# CMSIS-DAP_JX_copy.net
KiCad netlist of a schematic drawn in Altium Designer
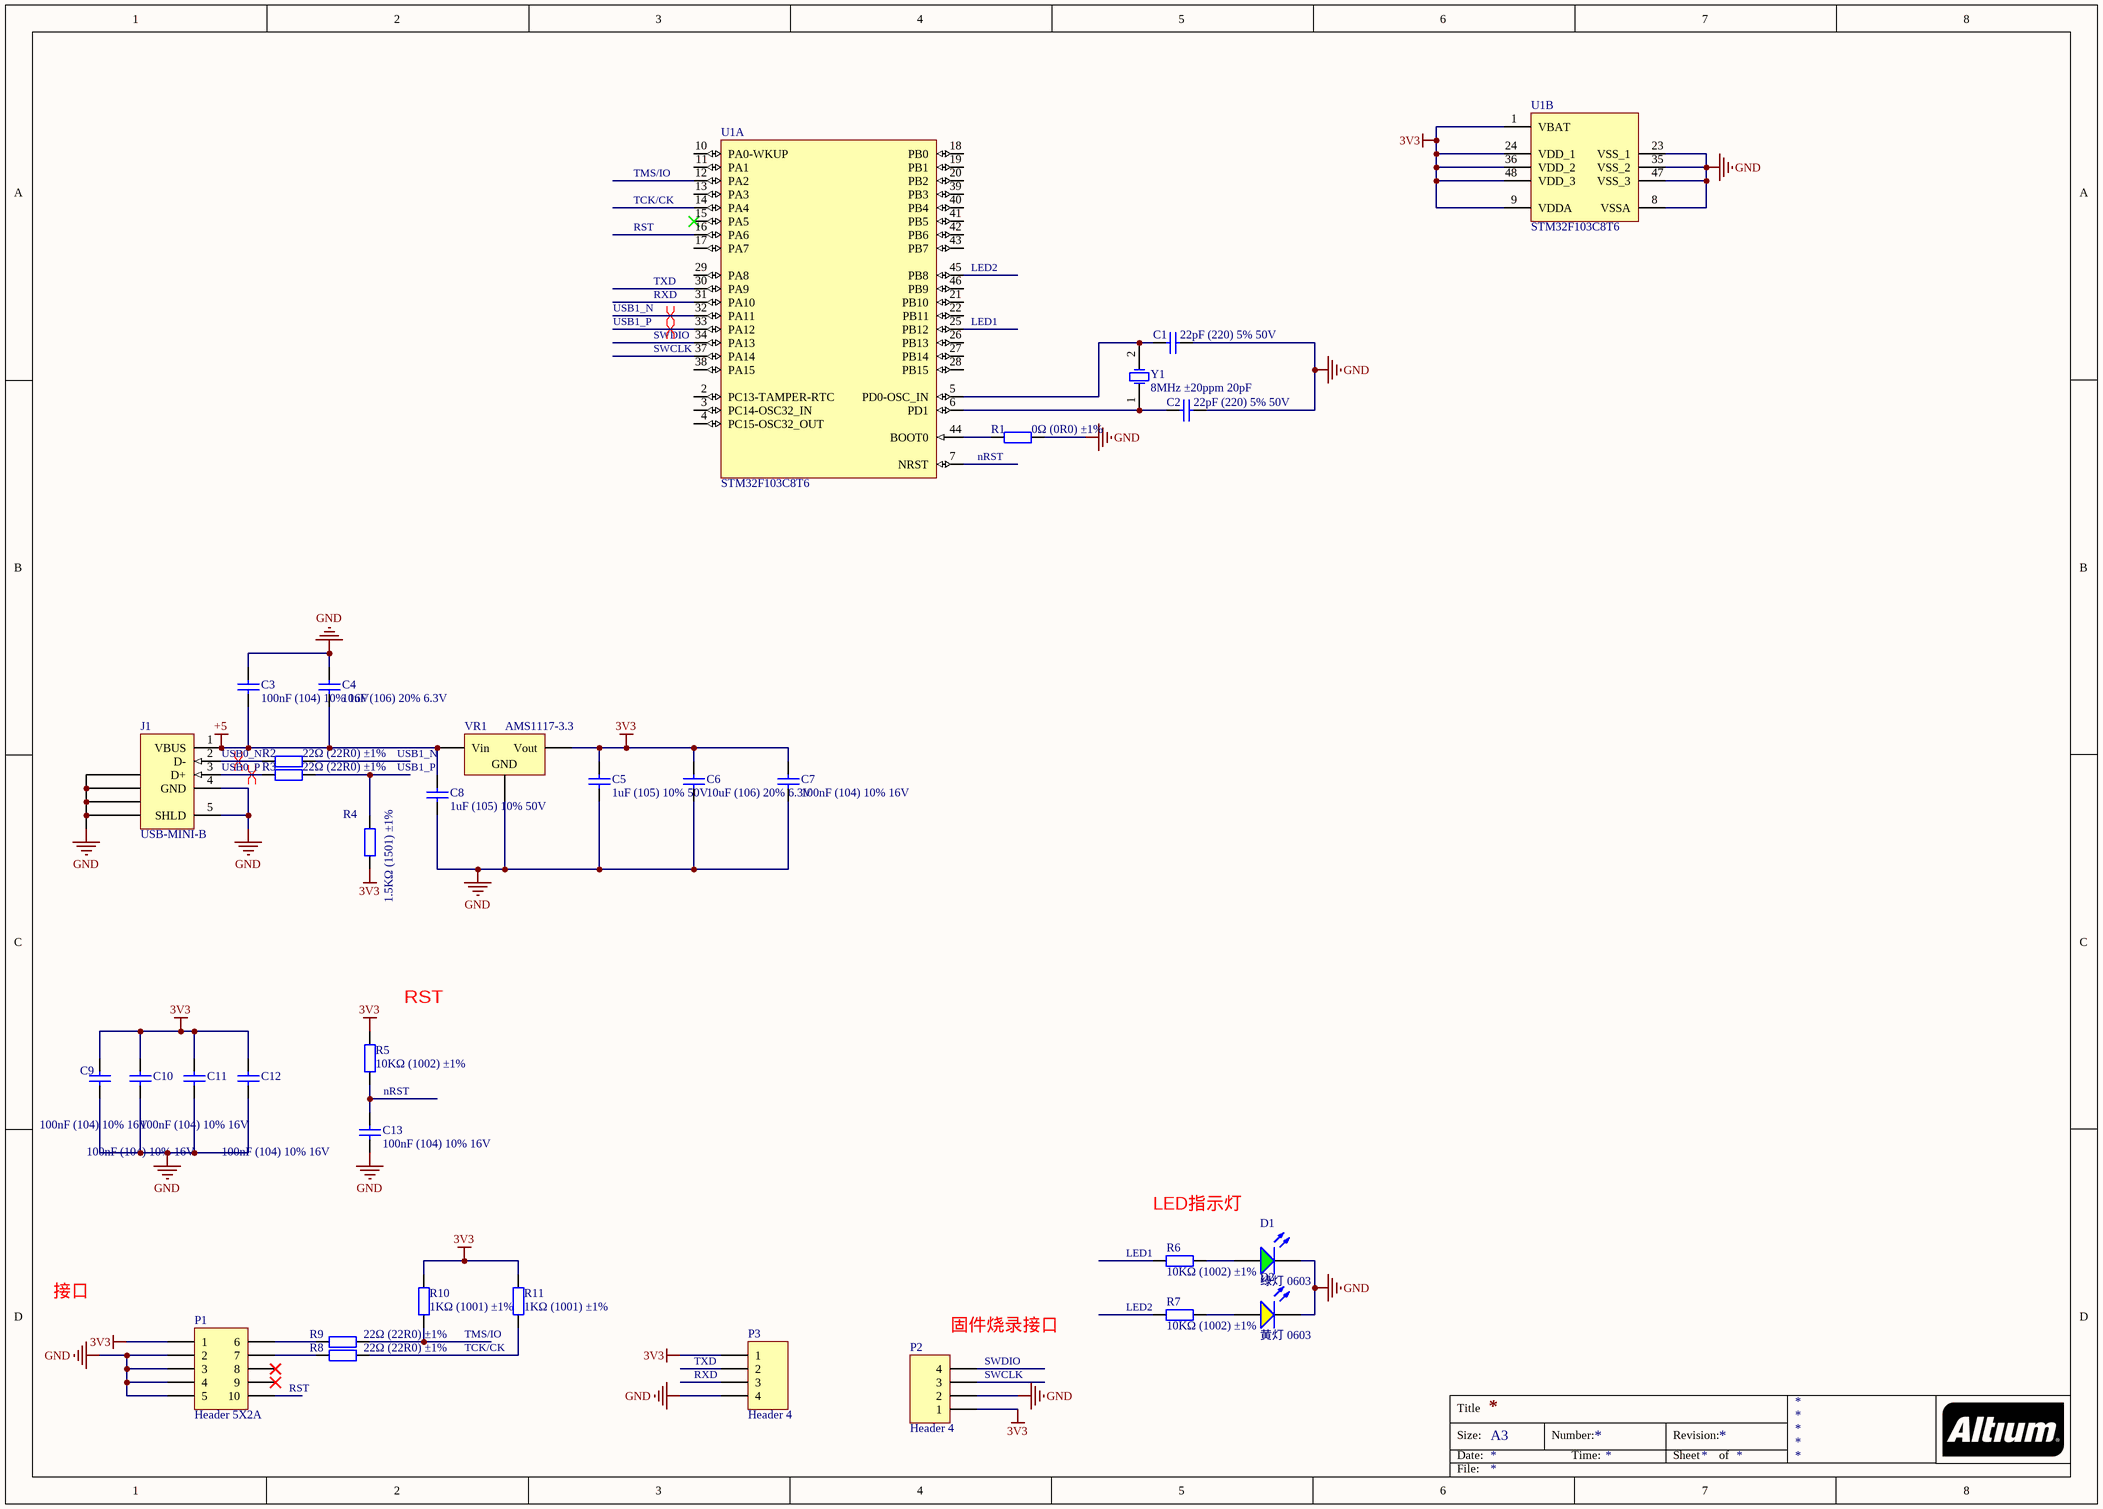
[diagram p0: CMSIS-DAP_JX+copy.schdoc]

(export (version "E")
  (design (tool "Eeschema 10.0.6"))
  (components
    (comp (ref "C1")
      (value "22pF (220) 5% 50V")
      (footprint "0402_C")
      (description "贴片电容")
      (libsource (lib "Miscellaneous Devices LC") (part "0402 22pF (220) 5% 50V"))
    )
    (comp (ref "C2")
      (value "22pF (220) 5% 50V")
      (footprint "0402_C")
      (description "贴片电容")
      (libsource (lib "Miscellaneous Devices LC") (part "0402 22pF (220) 5% 50V"))
    )
    (comp (ref "C3")
      (value "100nF (104) 10% 16V")
      (footprint "0402_C")
      (description "贴片电容")
      (libsource (lib "Miscellaneous Devices LC") (part "0402 100nF (104) 10% 16V"))
    )
    (comp (ref "C4")
      (value "10uF (106) 20% 6.3V")
      (footprint "0402_C")
      (description "贴片电容")
      (libsource (lib "Miscellaneous Devices LC") (part "0402 10uF (106) 20% 6.3V"))
    )
    (comp (ref "C5")
      (value "1uF (105) 10% 50V")
      (footprint "0603_C")
      (description "贴片电容")
      (libsource (lib "Miscellaneous Devices LC") (part "0603 1uF (105) 10% 50V"))
    )
    (comp (ref "C6")
      (value "10uF (106) 20% 6.3V")
      (footprint "0402_C")
      (description "贴片电容")
      (libsource (lib "Miscellaneous Devices LC") (part "0402 10uF (106) 20% 6.3V"))
    )
    (comp (ref "C7")
      (value "100nF (104) 10% 16V")
      (footprint "0402_C")
      (description "贴片电容")
      (libsource (lib "Miscellaneous Devices LC") (part "0402 100nF (104) 10% 16V"))
    )
    (comp (ref "C8")
      (value "1uF (105) 10% 50V")
      (footprint "0603_C")
      (description "贴片电容")
      (libsource (lib "Miscellaneous Devices LC") (part "0603 1uF (105) 10% 50V"))
    )
    (comp (ref "C9")
      (value "100nF (104) 10% 16V")
      (footprint "0402_C")
      (description "贴片电容")
      (libsource (lib "Miscellaneous Devices LC") (part "0402 100nF (104) 10% 16V"))
    )
    (comp (ref "C10")
      (value "100nF (104) 10% 16V")
      (footprint "0402_C")
      (description "贴片电容")
      (libsource (lib "Miscellaneous Devices LC") (part "0402 100nF (104) 10% 16V"))
    )
    (comp (ref "C11")
      (value "100nF (104) 10% 16V")
      (footprint "0402_C")
      (description "贴片电容")
      (libsource (lib "Miscellaneous Devices LC") (part "0402 100nF (104) 10% 16V"))
    )
    (comp (ref "C12")
      (value "100nF (104) 10% 16V")
      (footprint "0402_C")
      (description "贴片电容")
      (libsource (lib "Miscellaneous Devices LC") (part "0402 100nF (104) 10% 16V"))
    )
    (comp (ref "C13")
      (value "100nF (104) 10% 16V")
      (footprint "0402_C")
      (description "贴片电容")
      (libsource (lib "Miscellaneous Devices LC") (part "0402 100nF (104) 10% 16V"))
    )
    (comp (ref "D1")
      (value "绿灯 0603")
      (footprint "0603_LED_S1")
      (description "发光二极管")
      (libsource (lib "Miscellaneous Devices LC") (part "0603 绿灯"))
    )
    (comp (ref "D2")
      (value "黄灯 0603")
      (footprint "0603_LED_S1")
      (description "发光二极管")
      (libsource (lib "Miscellaneous Devices LC") (part "0603 黄灯"))
    )
    (comp (ref "J1")
      (value "USB-MINI-B")
      (footprint "U-G-04WD-W-01 公头")
      (description "USB 2.0, Right Angle, SMT, A Type, Receptacle, 5 Position, Black")
      (fields (field (name "PUBLISHER") "Altium Limited"))
      (libsource (lib "Sparks") (part "USB-MINI-B"))
    )
    (comp (ref "P1")
      (value "Header 5X2A")
      (footprint "SMT HEADER 5*2")
      (description "Header, 5-Pin, Dual row")
      (fields (field (name "PUBLISHER") "Altium Limited"))
      (libsource (lib "Miscellaneous Connectors") (part "Header 5X2A"))
    )
    (comp (ref "P2")
      (value "Header 4")
      (footprint "HDR1X4")
      (description "Header, 4-Pin")
      (fields (field (name "PUBLISHER") "Altium Limited"))
      (libsource (lib "") (part "Header 4_1"))
    )
    (comp (ref "P3")
      (value "Header 4")
      (footprint "HDR1X4")
      (description "Header, 4-Pin")
      (fields (field (name "PUBLISHER") "Altium Limited"))
      (libsource (lib "Sparks") (part "Header 4"))
    )
    (comp (ref "R1")
      (value "0Ω (0R0) ±1%")
      (footprint "0402_R")
      (description "贴片电阻")
      (libsource (lib "Miscellaneous Devices LC") (part "0402 0Ω (0R0) 1%"))
    )
    (comp (ref "R2")
      (value "22Ω (22R0) ±1%")
      (footprint "0402_R")
      (description "贴片电阻")
      (libsource (lib "Miscellaneous Devices LC") (part "0402 22Ω (22R0) 1%"))
    )
    (comp (ref "R3")
      (value "22Ω (22R0) ±1%")
      (footprint "0402_R")
      (description "贴片电阻")
      (libsource (lib "Miscellaneous Devices LC") (part "0402 22Ω (22R0) 1%"))
    )
    (comp (ref "R4")
      (value "1.5KΩ (1501) ±1%")
      (footprint "0402_R")
      (description "贴片电阻")
      (libsource (lib "Miscellaneous Devices LC") (part "0402 1.5KΩ (1501) 1%"))
    )
    (comp (ref "R5")
      (value "10KΩ (1002) ±1%")
      (footprint "0402_R")
      (description "贴片电阻")
      (libsource (lib "Miscellaneous Devices LC") (part "0402 10KΩ (1002) 1%"))
    )
    (comp (ref "R6")
      (value "10KΩ (1002) ±1%")
      (footprint "0402_R")
      (description "贴片电阻")
      (libsource (lib "") (part "0402 10KΩ (1002) 1%_1"))
    )
    (comp (ref "R7")
      (value "10KΩ (1002) ±1%")
      (footprint "0402_R")
      (description "贴片电阻")
      (libsource (lib "") (part "0402 10KΩ (1002) 1%_1"))
    )
    (comp (ref "R8")
      (value "22Ω (22R0) ±1%")
      (footprint "0402_R")
      (description "贴片电阻")
      (libsource (lib "Miscellaneous Devices LC") (part "0402 22Ω (22R0) 1%"))
    )
    (comp (ref "R9")
      (value "22Ω (22R0) ±1%")
      (footprint "0402_R")
      (description "贴片电阻")
      (libsource (lib "Miscellaneous Devices LC") (part "0402 22Ω (22R0) 1%"))
    )
    (comp (ref "R10")
      (value "1KΩ (1001) ±1%")
      (footprint "0402_R")
      (description "贴片电阻")
      (libsource (lib "Miscellaneous Devices LC") (part "0402 1KΩ (1001) 1%"))
    )
    (comp (ref "R11")
      (value "1KΩ (1001) ±1%")
      (footprint "0402_R")
      (description "贴片电阻")
      (libsource (lib "Miscellaneous Devices LC") (part "0402 1KΩ (1001) 1%"))
    )
    (comp (ref "U1")
      (value "STM32F103C8T6")
      (footprint "LQFP-48_7x7x05P")
      (description "ARM")
      (libsource (lib "Miscellaneous Devices LC") (part "STM32F103C8T6"))
    )
    (comp (ref "VR1")
      (value "AMS1117-3.3")
      (footprint "SOT-223")
      (description "低压差线性稳压(LDO)")
      (libsource (lib "Miscellaneous Devices LC") (part "SOT-223 AMS1117-3.3"))
    )
    (comp (ref "Y1")
      (value "8MHz ±20ppm 20pF")
      (footprint "SMD-5032_2P")
      (description "贴片晶振")
      (libsource (lib "Miscellaneous Devices LC") (part "SMD-5032_2P 8MHz 20ppm 20pF"))
    )
  )
  (nets
    (net (code "1") (name "+5") (class "Default")
      (node (ref "C3") (pin "1") (pinfunction "1_1") (pintype "passive"))
      (node (ref "C4") (pin "1") (pinfunction "1_1") (pintype "passive"))
      (node (ref "C8") (pin "2") (pinfunction "2_2") (pintype "passive"))
      (node (ref "J1") (pin "1") (pinfunction "VBUS_1") (pintype "power_in"))
      (node (ref "VR1") (pin "3") (pinfunction "Vin_3") (pintype "passive"))
    )
    (net (code "2") (name "/LED1") (class "Default")
      (node (ref "R6") (pin "1") (pinfunction "1_1") (pintype "passive"))
      (node (ref "U1") (pin "25") (pinfunction "PB12_25") (pintype "bidirectional"))
    )
    (net (code "3") (name "/LED2") (class "Default")
      (node (ref "R7") (pin "1") (pinfunction "1_1") (pintype "passive"))
      (node (ref "U1") (pin "45") (pinfunction "PB8_45") (pintype "bidirectional"))
    )
    (net (code "4") (name "/RST") (class "Default")
      (node (ref "P1") (pin "10") (pinfunction "10_10") (pintype "passive"))
      (node (ref "U1") (pin "16") (pinfunction "PA6_16") (pintype "bidirectional"))
    )
    (net (code "5") (name "/RXD") (class "Default")
      (node (ref "P3") (pin "3") (pinfunction "3_3") (pintype "passive"))
      (node (ref "U1") (pin "31") (pinfunction "PA10_31") (pintype "bidirectional"))
    )
    (net (code "6") (name "/SWCLK") (class "Default")
      (node (ref "P2") (pin "3") (pinfunction "3_3") (pintype "passive"))
      (node (ref "U1") (pin "37") (pinfunction "PA14_37") (pintype "bidirectional"))
    )
    (net (code "7") (name "/SWDIO") (class "Default")
      (node (ref "P2") (pin "4") (pinfunction "4_4") (pintype "passive"))
      (node (ref "U1") (pin "34") (pinfunction "PA13_34") (pintype "bidirectional"))
    )
    (net (code "8") (name "/TCK{slash}CK") (class "Default")
      (node (ref "R11") (pin "1") (pinfunction "1_1") (pintype "passive"))
      (node (ref "R8") (pin "2") (pinfunction "2_2") (pintype "passive"))
      (node (ref "U1") (pin "14") (pinfunction "PA4_14") (pintype "bidirectional"))
    )
    (net (code "9") (name "/TMS{slash}IO") (class "Default")
      (node (ref "R10") (pin "1") (pinfunction "1_1") (pintype "passive"))
      (node (ref "R9") (pin "2") (pinfunction "2_2") (pintype "passive"))
      (node (ref "U1") (pin "12") (pinfunction "PA2_12") (pintype "bidirectional"))
    )
    (net (code "10") (name "/TXD") (class "Default")
      (node (ref "P3") (pin "2") (pinfunction "2_2") (pintype "passive"))
      (node (ref "U1") (pin "30") (pinfunction "PA9_30") (pintype "bidirectional"))
    )
    (net (code "11") (name "/USB0_N") (class "Default")
      (node (ref "J1") (pin "2") (pinfunction "D-_2") (pintype "input"))
      (node (ref "R2") (pin "1") (pinfunction "1_1") (pintype "passive"))
    )
    (net (code "12") (name "/USB0_P") (class "Default")
      (node (ref "J1") (pin "3") (pinfunction "D+_3") (pintype "input"))
      (node (ref "R3") (pin "1") (pinfunction "1_1") (pintype "passive"))
    )
    (net (code "13") (name "/USB1_N") (class "Default")
      (node (ref "R2") (pin "2") (pinfunction "2_2") (pintype "passive"))
      (node (ref "U1") (pin "32") (pinfunction "PA11_32") (pintype "bidirectional"))
    )
    (net (code "14") (name "/USB1_P") (class "Default")
      (node (ref "R3") (pin "2") (pinfunction "2_2") (pintype "passive"))
      (node (ref "R4") (pin "2") (pinfunction "2_2") (pintype "passive"))
      (node (ref "U1") (pin "33") (pinfunction "PA12_33") (pintype "bidirectional"))
    )
    (net (code "15") (name "/nRST") (class "Default")
      (node (ref "C13") (pin "2") (pinfunction "2_2") (pintype "passive"))
      (node (ref "R5") (pin "1") (pinfunction "1_1") (pintype "passive"))
      (node (ref "U1") (pin "7") (pinfunction "NRST_7") (pintype "bidirectional"))
    )
    (net (code "16") (name "3V3") (class "Default")
      (node (ref "C10") (pin "2") (pinfunction "2_2") (pintype "passive"))
      (node (ref "C11") (pin "2") (pinfunction "2_2") (pintype "passive"))
      (node (ref "C12") (pin "2") (pinfunction "2_2") (pintype "passive"))
      (node (ref "C5") (pin "2") (pinfunction "2_2") (pintype "passive"))
      (node (ref "C6") (pin "2") (pinfunction "2_2") (pintype "passive"))
      (node (ref "C7") (pin "2") (pinfunction "2_2") (pintype "passive"))
      (node (ref "C9") (pin "2") (pinfunction "2_2") (pintype "passive"))
      (node (ref "P1") (pin "1") (pinfunction "1_1") (pintype "passive"))
      (node (ref "P2") (pin "1") (pinfunction "1_1") (pintype "passive"))
      (node (ref "P3") (pin "1") (pinfunction "1_1") (pintype "passive"))
      (node (ref "R10") (pin "2") (pinfunction "2_2") (pintype "passive"))
      (node (ref "R11") (pin "2") (pinfunction "2_2") (pintype "passive"))
      (node (ref "R4") (pin "1") (pinfunction "1_1") (pintype "passive"))
      (node (ref "R5") (pin "2") (pinfunction "2_2") (pintype "passive"))
      (node (ref "U1") (pin "1") (pinfunction "VBAT_1") (pintype "power_in"))
      (node (ref "U1") (pin "24") (pinfunction "VDD_1_24") (pintype "power_in"))
      (node (ref "U1") (pin "36") (pinfunction "VDD_2_36") (pintype "power_in"))
      (node (ref "U1") (pin "48") (pinfunction "VDD_3_48") (pintype "power_in"))
      (node (ref "U1") (pin "9") (pinfunction "VDDA_9") (pintype "power_in"))
      (node (ref "VR1") (pin "2") (pinfunction "Vout_2") (pintype "passive"))
    )
    (net (code "17") (name "GND") (class "Default")
      (node (ref "C1") (pin "2") (pinfunction "2_2") (pintype "passive"))
      (node (ref "C10") (pin "1") (pinfunction "1_1") (pintype "passive"))
      (node (ref "C11") (pin "1") (pinfunction "1_1") (pintype "passive"))
      (node (ref "C12") (pin "1") (pinfunction "1_1") (pintype "passive"))
      (node (ref "C13") (pin "1") (pinfunction "1_1") (pintype "passive"))
      (node (ref "C2") (pin "2") (pinfunction "2_2") (pintype "passive"))
      (node (ref "C3") (pin "2") (pinfunction "2_2") (pintype "passive"))
      (node (ref "C4") (pin "2") (pinfunction "2_2") (pintype "passive"))
      (node (ref "C5") (pin "1") (pinfunction "1_1") (pintype "passive"))
      (node (ref "C6") (pin "1") (pinfunction "1_1") (pintype "passive"))
      (node (ref "C7") (pin "1") (pinfunction "1_1") (pintype "passive"))
      (node (ref "C8") (pin "1") (pinfunction "1_1") (pintype "passive"))
      (node (ref "C9") (pin "1") (pinfunction "1_1") (pintype "passive"))
      (node (ref "D1") (pin "K") (pinfunction "K_K") (pintype "passive"))
      (node (ref "D2") (pin "K") (pinfunction "K_K") (pintype "passive"))
      (node (ref "J1") (pin "4") (pinfunction "GND_4") (pintype "power_in"))
      (node (ref "J1") (pin "5") (pinfunction "SHLD_5") (pintype "passive"))
      (node (ref "J1") (pin "6") (pinfunction "SHLD_6") (pintype "passive"))
      (node (ref "J1") (pin "7") (pinfunction "SHLD_7") (pintype "passive"))
      (node (ref "J1") (pin "8") (pinfunction "SHLD_8") (pintype "passive"))
      (node (ref "J1") (pin "9") (pinfunction "SHLD_9") (pintype "passive"))
      (node (ref "P1") (pin "2") (pinfunction "2_2") (pintype "passive"))
      (node (ref "P1") (pin "3") (pinfunction "3_3") (pintype "passive"))
      (node (ref "P1") (pin "4") (pinfunction "4_4") (pintype "passive"))
      (node (ref "P1") (pin "5") (pinfunction "5_5") (pintype "passive"))
      (node (ref "P2") (pin "2") (pinfunction "2_2") (pintype "passive"))
      (node (ref "P3") (pin "4") (pinfunction "4_4") (pintype "passive"))
      (node (ref "R1") (pin "2") (pinfunction "2_2") (pintype "passive"))
      (node (ref "U1") (pin "23") (pinfunction "VSS_1_23") (pintype "power_in"))
      (node (ref "U1") (pin "35") (pinfunction "VSS_2_35") (pintype "power_in"))
      (node (ref "U1") (pin "47") (pinfunction "VSS_3_47") (pintype "power_in"))
      (node (ref "U1") (pin "8") (pinfunction "VSSA_8") (pintype "power_in"))
      (node (ref "VR1") (pin "1") (pinfunction "GND_1") (pintype "passive"))
    )
    (net (code "18") (name "Net-(D1-PadA)") (class "Default")
      (node (ref "D1") (pin "A") (pinfunction "A_A") (pintype "passive"))
      (node (ref "R6") (pin "2") (pinfunction "2_2") (pintype "passive"))
    )
    (net (code "19") (name "Net-(D2-PadA)") (class "Default")
      (node (ref "D2") (pin "A") (pinfunction "A_A") (pintype "passive"))
      (node (ref "R7") (pin "2") (pinfunction "2_2") (pintype "passive"))
    )
    (net (code "20") (name "Net-(P1-Pad6)") (class "Default")
      (node (ref "P1") (pin "6") (pinfunction "6_6") (pintype "passive"))
      (node (ref "R9") (pin "1") (pinfunction "1_1") (pintype "passive"))
    )
    (net (code "21") (name "Net-(P1-Pad7)") (class "Default")
      (node (ref "P1") (pin "7") (pinfunction "7_7") (pintype "passive"))
      (node (ref "R8") (pin "1") (pinfunction "1_1") (pintype "passive"))
    )
    (net (code "22") (name "Net-(U1A-BOOT0)") (class "Default")
      (node (ref "R1") (pin "1") (pinfunction "1_1") (pintype "passive"))
      (node (ref "U1") (pin "44") (pinfunction "BOOT0_44") (pintype "input"))
    )
    (net (code "23") (name "Net-(U1A-PD0-OSC_IN)") (class "Default")
      (node (ref "C1") (pin "1") (pinfunction "1_1") (pintype "passive"))
      (node (ref "U1") (pin "5") (pinfunction "PD0-OSC_IN_5") (pintype "bidirectional"))
      (node (ref "Y1") (pin "2") (pinfunction "OSC2_2") (pintype "passive"))
    )
    (net (code "24") (name "Net-(U1A-PD1)") (class "Default")
      (node (ref "C2") (pin "1") (pinfunction "1_1") (pintype "passive"))
      (node (ref "U1") (pin "6") (pinfunction "PD1_6") (pintype "bidirectional"))
      (node (ref "Y1") (pin "1") (pinfunction "OSC1_1") (pintype "passive"))
    )
    (net (code "25") (name "unconnected-(P1-Pad8)") (class "Default")
      (node (ref "P1") (pin "8") (pinfunction "8_8") (pintype "passive+no_connect"))
    )
    (net (code "26") (name "unconnected-(P1-Pad9)") (class "Default")
      (node (ref "P1") (pin "9") (pinfunction "9_9") (pintype "passive+no_connect"))
    )
    (net (code "27") (name "unconnected-(U1A-PA0-WKUP-Pad10)") (class "Default")
      (node (ref "U1") (pin "10") (pinfunction "PA0-WKUP_10") (pintype "bidirectional"))
    )
    (net (code "28") (name "unconnected-(U1A-PA1-Pad11)") (class "Default")
      (node (ref "U1") (pin "11") (pinfunction "PA1_11") (pintype "bidirectional"))
    )
    (net (code "29") (name "unconnected-(U1A-PA3-Pad13)") (class "Default")
      (node (ref "U1") (pin "13") (pinfunction "PA3_13") (pintype "bidirectional"))
    )
    (net (code "30") (name "unconnected-(U1A-PA5-Pad15)") (class "Default")
      (node (ref "U1") (pin "15") (pinfunction "PA5_15") (pintype "bidirectional+no_connect"))
    )
    (net (code "31") (name "unconnected-(U1A-PA7-Pad17)") (class "Default")
      (node (ref "U1") (pin "17") (pinfunction "PA7_17") (pintype "bidirectional"))
    )
    (net (code "32") (name "unconnected-(U1A-PA8-Pad29)") (class "Default")
      (node (ref "U1") (pin "29") (pinfunction "PA8_29") (pintype "bidirectional"))
    )
    (net (code "33") (name "unconnected-(U1A-PA15-Pad38)") (class "Default")
      (node (ref "U1") (pin "38") (pinfunction "PA15_38") (pintype "bidirectional"))
    )
    (net (code "34") (name "unconnected-(U1A-PB0-Pad18)") (class "Default")
      (node (ref "U1") (pin "18") (pinfunction "PB0_18") (pintype "bidirectional"))
    )
    (net (code "35") (name "unconnected-(U1A-PB1-Pad19)") (class "Default")
      (node (ref "U1") (pin "19") (pinfunction "PB1_19") (pintype "bidirectional"))
    )
    (net (code "36") (name "unconnected-(U1A-PB2-Pad20)") (class "Default")
      (node (ref "U1") (pin "20") (pinfunction "PB2_20") (pintype "bidirectional"))
    )
    (net (code "37") (name "unconnected-(U1A-PB3-Pad39)") (class "Default")
      (node (ref "U1") (pin "39") (pinfunction "PB3_39") (pintype "bidirectional"))
    )
    (net (code "38") (name "unconnected-(U1A-PB4-Pad40)") (class "Default")
      (node (ref "U1") (pin "40") (pinfunction "PB4_40") (pintype "bidirectional"))
    )
    (net (code "39") (name "unconnected-(U1A-PB5-Pad41)") (class "Default")
      (node (ref "U1") (pin "41") (pinfunction "PB5_41") (pintype "bidirectional"))
    )
    (net (code "40") (name "unconnected-(U1A-PB6-Pad42)") (class "Default")
      (node (ref "U1") (pin "42") (pinfunction "PB6_42") (pintype "bidirectional"))
    )
    (net (code "41") (name "unconnected-(U1A-PB7-Pad43)") (class "Default")
      (node (ref "U1") (pin "43") (pinfunction "PB7_43") (pintype "bidirectional"))
    )
    (net (code "42") (name "unconnected-(U1A-PB9-Pad46)") (class "Default")
      (node (ref "U1") (pin "46") (pinfunction "PB9_46") (pintype "bidirectional"))
    )
    (net (code "43") (name "unconnected-(U1A-PB10-Pad21)") (class "Default")
      (node (ref "U1") (pin "21") (pinfunction "PB10_21") (pintype "bidirectional"))
    )
    (net (code "44") (name "unconnected-(U1A-PB11-Pad22)") (class "Default")
      (node (ref "U1") (pin "22") (pinfunction "PB11_22") (pintype "bidirectional"))
    )
    (net (code "45") (name "unconnected-(U1A-PB13-Pad26)") (class "Default")
      (node (ref "U1") (pin "26") (pinfunction "PB13_26") (pintype "bidirectional"))
    )
    (net (code "46") (name "unconnected-(U1A-PB14-Pad27)") (class "Default")
      (node (ref "U1") (pin "27") (pinfunction "PB14_27") (pintype "bidirectional"))
    )
    (net (code "47") (name "unconnected-(U1A-PB15-Pad28)") (class "Default")
      (node (ref "U1") (pin "28") (pinfunction "PB15_28") (pintype "bidirectional"))
    )
    (net (code "48") (name "unconnected-(U1A-PC13-TAMPER-RTC-Pad2)") (class "Default")
      (node (ref "U1") (pin "2") (pinfunction "PC13-TAMPER-RTC_2") (pintype "bidirectional"))
    )
    (net (code "49") (name "unconnected-(U1A-PC14-OSC32_IN-Pad3)") (class "Default")
      (node (ref "U1") (pin "3") (pinfunction "PC14-OSC32_IN_3") (pintype "bidirectional"))
    )
    (net (code "50") (name "unconnected-(U1A-PC15-OSC32_OUT-Pad4)") (class "Default")
      (node (ref "U1") (pin "4") (pinfunction "PC15-OSC32_OUT_4") (pintype "bidirectional"))
    )
  )
)
